# HSMC.net
KiCad netlist of a schematic drawn in Altium Designer
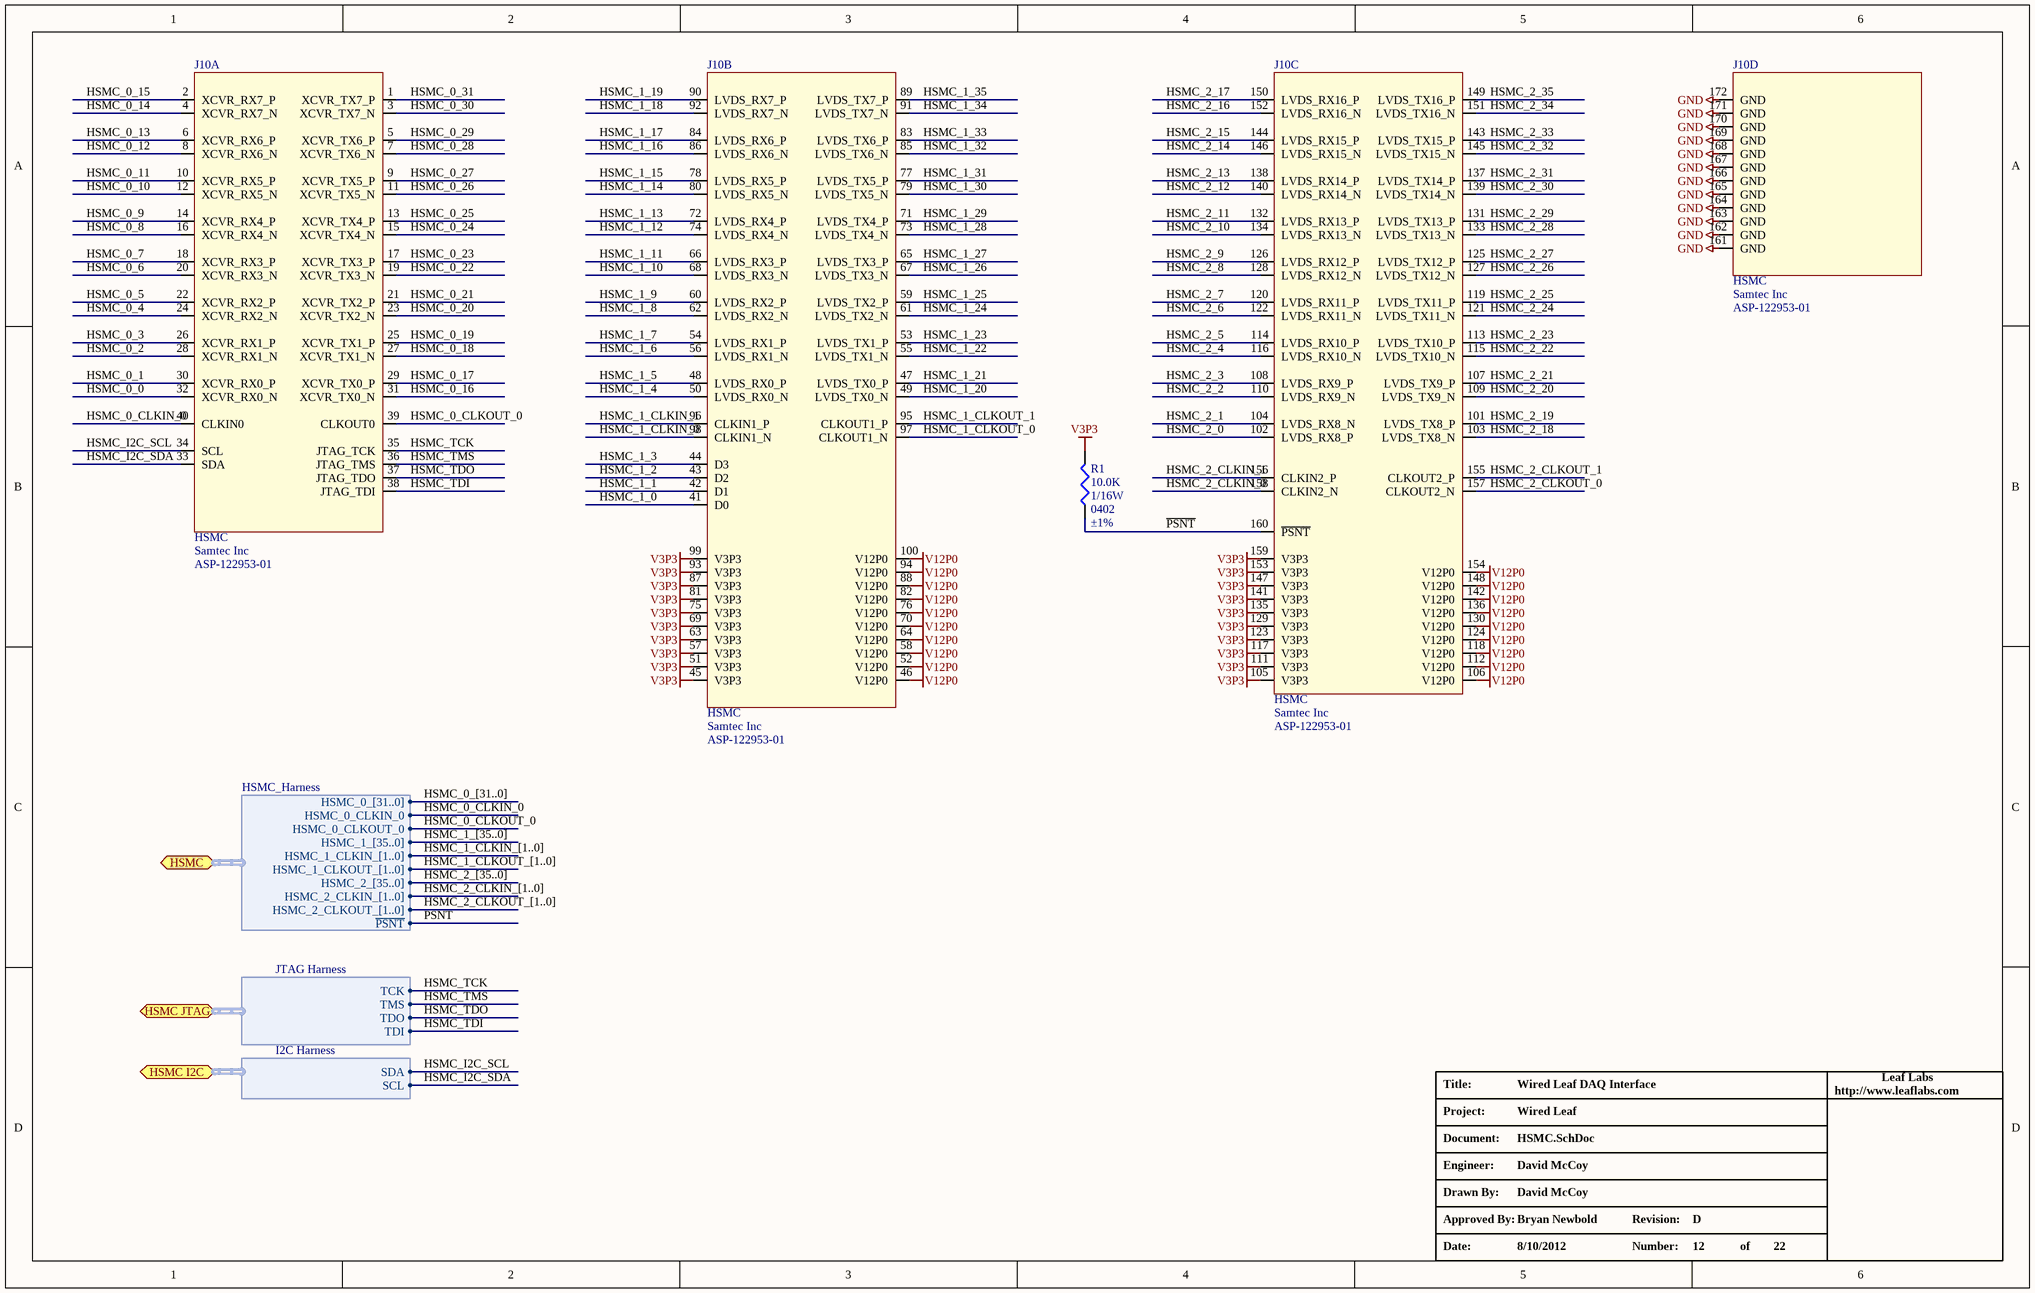
[diagram p0: HSMC.SchDoc]

(export (version "E")
  (design (tool "Eeschema 10.0.6"))
  (components
    (comp (ref "J10")
      (value "HSMC")
      (footprint "ASP-122953-01-ND")
      (description "CONN RECPT 60POS .020\" SMT GOLD")
      (fields
        (field (name "MANUFACTURER") "Samtec Inc")
        (field (name "MANUFACTURER PART NUMBER") "ASP-122953-01")
      )
      (libsource (lib "Main LibraryX") (part "J_HSMC"))
    )
    (comp (ref "R1")
      (value "R_0402_10.0K")
      (footprint "ERA-0402")
      (description "RES 10.0K OHM 1/16W 1% 0402 SMD")
      (fields
        (field (name "MANUFACTURER") "Vishay/Dale")
        (field (name "MANUFACTURER PART NUMBER") "CRCW040210K0FKED")
        (field (name "RESISTANCE IN OHMS") "10.0K")
        (field (name "POWER (WATTS)") "1/16W")
        (field (name "CASE") "0402")
        (field (name "TOLERANCE") "±1%")
      )
      (libsource (lib "Main Library") (part "R_0402_10.0K"))
    )
  )
  (nets
    (net (code "5") (name "/HSMC_0_0") (class "Default")
      (node (ref "J10") (pin "32") (pinfunction "XCVR_RX0_N_32") (pintype "passive"))
    )
    (net (code "6") (name "/HSMC_0_1") (class "Default")
      (node (ref "J10") (pin "30") (pinfunction "XCVR_RX0_P_30") (pintype "passive"))
    )
    (net (code "7") (name "/HSMC_0_2") (class "Default")
      (node (ref "J10") (pin "28") (pinfunction "XCVR_RX1_N_28") (pintype "passive"))
    )
    (net (code "8") (name "/HSMC_0_3") (class "Default")
      (node (ref "J10") (pin "26") (pinfunction "XCVR_RX1_P_26") (pintype "passive"))
    )
    (net (code "9") (name "/HSMC_0_4") (class "Default")
      (node (ref "J10") (pin "24") (pinfunction "XCVR_RX2_N_24") (pintype "passive"))
    )
    (net (code "10") (name "/HSMC_0_5") (class "Default")
      (node (ref "J10") (pin "22") (pinfunction "XCVR_RX2_P_22") (pintype "passive"))
    )
    (net (code "11") (name "/HSMC_0_6") (class "Default")
      (node (ref "J10") (pin "20") (pinfunction "XCVR_RX3_N_20") (pintype "passive"))
    )
    (net (code "12") (name "/HSMC_0_7") (class "Default")
      (node (ref "J10") (pin "18") (pinfunction "XCVR_RX3_P_18") (pintype "passive"))
    )
    (net (code "13") (name "/HSMC_0_8") (class "Default")
      (node (ref "J10") (pin "16") (pinfunction "XCVR_RX4_N_16") (pintype "passive"))
    )
    (net (code "14") (name "/HSMC_0_9") (class "Default")
      (node (ref "J10") (pin "14") (pinfunction "XCVR_RX4_P_14") (pintype "passive"))
    )
    (net (code "15") (name "/HSMC_0_10") (class "Default")
      (node (ref "J10") (pin "12") (pinfunction "XCVR_RX5_N_12") (pintype "passive"))
    )
    (net (code "16") (name "/HSMC_0_11") (class "Default")
      (node (ref "J10") (pin "10") (pinfunction "XCVR_RX5_P_10") (pintype "passive"))
    )
    (net (code "17") (name "/HSMC_0_12") (class "Default")
      (node (ref "J10") (pin "8") (pinfunction "XCVR_RX6_N_8") (pintype "passive"))
    )
    (net (code "18") (name "/HSMC_0_13") (class "Default")
      (node (ref "J10") (pin "6") (pinfunction "XCVR_RX6_P_6") (pintype "passive"))
    )
    (net (code "19") (name "/HSMC_0_14") (class "Default")
      (node (ref "J10") (pin "4") (pinfunction "XCVR_RX7_N_4") (pintype "passive"))
    )
    (net (code "20") (name "/HSMC_0_15") (class "Default")
      (node (ref "J10") (pin "2") (pinfunction "XCVR_RX7_P_2") (pintype "passive"))
    )
    (net (code "21") (name "/HSMC_0_16") (class "Default")
      (node (ref "J10") (pin "31") (pinfunction "XCVR_TX0_N_31") (pintype "passive"))
    )
    (net (code "22") (name "/HSMC_0_17") (class "Default")
      (node (ref "J10") (pin "29") (pinfunction "XCVR_TX0_P_29") (pintype "passive"))
    )
    (net (code "23") (name "/HSMC_0_18") (class "Default")
      (node (ref "J10") (pin "27") (pinfunction "XCVR_TX1_N_27") (pintype "passive"))
    )
    (net (code "24") (name "/HSMC_0_19") (class "Default")
      (node (ref "J10") (pin "25") (pinfunction "XCVR_TX1_P_25") (pintype "passive"))
    )
    (net (code "25") (name "/HSMC_0_20") (class "Default")
      (node (ref "J10") (pin "23") (pinfunction "XCVR_TX2_N_23") (pintype "passive"))
    )
    (net (code "26") (name "/HSMC_0_21") (class "Default")
      (node (ref "J10") (pin "21") (pinfunction "XCVR_TX2_P_21") (pintype "passive"))
    )
    (net (code "27") (name "/HSMC_0_22") (class "Default")
      (node (ref "J10") (pin "19") (pinfunction "XCVR_TX3_N_19") (pintype "passive"))
    )
    (net (code "28") (name "/HSMC_0_23") (class "Default")
      (node (ref "J10") (pin "17") (pinfunction "XCVR_TX3_P_17") (pintype "passive"))
    )
    (net (code "29") (name "/HSMC_0_24") (class "Default")
      (node (ref "J10") (pin "15") (pinfunction "XCVR_TX4_N_15") (pintype "passive"))
    )
    (net (code "30") (name "/HSMC_0_25") (class "Default")
      (node (ref "J10") (pin "13") (pinfunction "XCVR_TX4_P_13") (pintype "passive"))
    )
    (net (code "31") (name "/HSMC_0_26") (class "Default")
      (node (ref "J10") (pin "11") (pinfunction "XCVR_TX5_N_11") (pintype "passive"))
    )
    (net (code "32") (name "/HSMC_0_27") (class "Default")
      (node (ref "J10") (pin "9") (pinfunction "XCVR_TX5_P_9") (pintype "passive"))
    )
    (net (code "33") (name "/HSMC_0_28") (class "Default")
      (node (ref "J10") (pin "7") (pinfunction "XCVR_TX6_N_7") (pintype "passive"))
    )
    (net (code "34") (name "/HSMC_0_29") (class "Default")
      (node (ref "J10") (pin "5") (pinfunction "XCVR_TX6_P_5") (pintype "passive"))
    )
    (net (code "35") (name "/HSMC_0_30") (class "Default")
      (node (ref "J10") (pin "3") (pinfunction "XCVR_TX7_N_3") (pintype "passive"))
    )
    (net (code "36") (name "/HSMC_0_31") (class "Default")
      (node (ref "J10") (pin "1") (pinfunction "XCVR_TX7_P_1") (pintype "passive"))
    )
    (net (code "37") (name "/HSMC_0_CLKIN_0") (class "Default")
      (node (ref "J10") (pin "40") (pinfunction "CLKIN0_40") (pintype "passive"))
    )
    (net (code "38") (name "/HSMC_0_CLKOUT_0") (class "Default")
      (node (ref "J10") (pin "39") (pinfunction "CLKOUT0_39") (pintype "passive"))
    )
    (net (code "40") (name "/HSMC_1_0") (class "Default")
      (node (ref "J10") (pin "41") (pinfunction "D0_41") (pintype "passive"))
    )
    (net (code "41") (name "/HSMC_1_1") (class "Default")
      (node (ref "J10") (pin "42") (pinfunction "D1_42") (pintype "passive"))
    )
    (net (code "42") (name "/HSMC_1_2") (class "Default")
      (node (ref "J10") (pin "43") (pinfunction "D2_43") (pintype "passive"))
    )
    (net (code "43") (name "/HSMC_1_3") (class "Default")
      (node (ref "J10") (pin "44") (pinfunction "D3_44") (pintype "passive"))
    )
    (net (code "44") (name "/HSMC_1_4") (class "Default")
      (node (ref "J10") (pin "50") (pinfunction "LVDS_RX0_N_50") (pintype "passive"))
    )
    (net (code "45") (name "/HSMC_1_5") (class "Default")
      (node (ref "J10") (pin "48") (pinfunction "LVDS_RX0_P_48") (pintype "passive"))
    )
    (net (code "46") (name "/HSMC_1_6") (class "Default")
      (node (ref "J10") (pin "56") (pinfunction "LVDS_RX1_N_56") (pintype "passive"))
    )
    (net (code "47") (name "/HSMC_1_7") (class "Default")
      (node (ref "J10") (pin "54") (pinfunction "LVDS_RX1_P_54") (pintype "passive"))
    )
    (net (code "48") (name "/HSMC_1_8") (class "Default")
      (node (ref "J10") (pin "62") (pinfunction "LVDS_RX2_N_62") (pintype "passive"))
    )
    (net (code "49") (name "/HSMC_1_9") (class "Default")
      (node (ref "J10") (pin "60") (pinfunction "LVDS_RX2_P_60") (pintype "passive"))
    )
    (net (code "50") (name "/HSMC_1_10") (class "Default")
      (node (ref "J10") (pin "68") (pinfunction "LVDS_RX3_N_68") (pintype "passive"))
    )
    (net (code "51") (name "/HSMC_1_11") (class "Default")
      (node (ref "J10") (pin "66") (pinfunction "LVDS_RX3_P_66") (pintype "passive"))
    )
    (net (code "52") (name "/HSMC_1_12") (class "Default")
      (node (ref "J10") (pin "74") (pinfunction "LVDS_RX4_N_74") (pintype "passive"))
    )
    (net (code "53") (name "/HSMC_1_13") (class "Default")
      (node (ref "J10") (pin "72") (pinfunction "LVDS_RX4_P_72") (pintype "passive"))
    )
    (net (code "54") (name "/HSMC_1_14") (class "Default")
      (node (ref "J10") (pin "80") (pinfunction "LVDS_RX5_N_80") (pintype "passive"))
    )
    (net (code "55") (name "/HSMC_1_15") (class "Default")
      (node (ref "J10") (pin "78") (pinfunction "LVDS_RX5_P_78") (pintype "passive"))
    )
    (net (code "56") (name "/HSMC_1_16") (class "Default")
      (node (ref "J10") (pin "86") (pinfunction "LVDS_RX6_N_86") (pintype "passive"))
    )
    (net (code "57") (name "/HSMC_1_17") (class "Default")
      (node (ref "J10") (pin "84") (pinfunction "LVDS_RX6_P_84") (pintype "passive"))
    )
    (net (code "58") (name "/HSMC_1_18") (class "Default")
      (node (ref "J10") (pin "92") (pinfunction "LVDS_RX7_N_92") (pintype "passive"))
    )
    (net (code "59") (name "/HSMC_1_19") (class "Default")
      (node (ref "J10") (pin "90") (pinfunction "LVDS_RX7_P_90") (pintype "passive"))
    )
    (net (code "60") (name "/HSMC_1_20") (class "Default")
      (node (ref "J10") (pin "49") (pinfunction "LVDS_TX0_N_49") (pintype "passive"))
    )
    (net (code "61") (name "/HSMC_1_21") (class "Default")
      (node (ref "J10") (pin "47") (pinfunction "LVDS_TX0_P_47") (pintype "passive"))
    )
    (net (code "62") (name "/HSMC_1_22") (class "Default")
      (node (ref "J10") (pin "55") (pinfunction "LVDS_TX1_N_55") (pintype "passive"))
    )
    (net (code "63") (name "/HSMC_1_23") (class "Default")
      (node (ref "J10") (pin "53") (pinfunction "LVDS_TX1_P_53") (pintype "passive"))
    )
    (net (code "64") (name "/HSMC_1_24") (class "Default")
      (node (ref "J10") (pin "61") (pinfunction "LVDS_TX2_N_61") (pintype "passive"))
    )
    (net (code "65") (name "/HSMC_1_25") (class "Default")
      (node (ref "J10") (pin "59") (pinfunction "LVDS_TX2_P_59") (pintype "passive"))
    )
    (net (code "66") (name "/HSMC_1_26") (class "Default")
      (node (ref "J10") (pin "67") (pinfunction "LVDS_TX3_N_67") (pintype "passive"))
    )
    (net (code "67") (name "/HSMC_1_27") (class "Default")
      (node (ref "J10") (pin "65") (pinfunction "LVDS_TX3_P_65") (pintype "passive"))
    )
    (net (code "68") (name "/HSMC_1_28") (class "Default")
      (node (ref "J10") (pin "73") (pinfunction "LVDS_TX4_N_73") (pintype "passive"))
    )
    (net (code "69") (name "/HSMC_1_29") (class "Default")
      (node (ref "J10") (pin "71") (pinfunction "LVDS_TX4_P_71") (pintype "passive"))
    )
    (net (code "70") (name "/HSMC_1_30") (class "Default")
      (node (ref "J10") (pin "79") (pinfunction "LVDS_TX5_N_79") (pintype "passive"))
    )
    (net (code "71") (name "/HSMC_1_31") (class "Default")
      (node (ref "J10") (pin "77") (pinfunction "LVDS_TX5_P_77") (pintype "passive"))
    )
    (net (code "72") (name "/HSMC_1_32") (class "Default")
      (node (ref "J10") (pin "85") (pinfunction "LVDS_TX6_N_85") (pintype "passive"))
    )
    (net (code "73") (name "/HSMC_1_33") (class "Default")
      (node (ref "J10") (pin "83") (pinfunction "LVDS_TX6_P_83") (pintype "passive"))
    )
    (net (code "74") (name "/HSMC_1_34") (class "Default")
      (node (ref "J10") (pin "91") (pinfunction "LVDS_TX7_N_91") (pintype "passive"))
    )
    (net (code "75") (name "/HSMC_1_35") (class "Default")
      (node (ref "J10") (pin "89") (pinfunction "LVDS_TX7_P_89") (pintype "passive"))
    )
    (net (code "76") (name "/HSMC_1_CLKIN_0") (class "Default")
      (node (ref "J10") (pin "98") (pinfunction "CLKIN1_N_98") (pintype "passive"))
    )
    (net (code "77") (name "/HSMC_1_CLKIN_1") (class "Default")
      (node (ref "J10") (pin "96") (pinfunction "CLKIN1_P_96") (pintype "passive"))
    )
    (net (code "79") (name "/HSMC_1_CLKOUT_0") (class "Default")
      (node (ref "J10") (pin "97") (pinfunction "CLKOUT1_N_97") (pintype "passive"))
    )
    (net (code "80") (name "/HSMC_1_CLKOUT_1") (class "Default")
      (node (ref "J10") (pin "95") (pinfunction "CLKOUT1_P_95") (pintype "passive"))
    )
    (net (code "83") (name "/HSMC_2_0") (class "Default")
      (node (ref "J10") (pin "102") (pinfunction "LVDS_RX8_P_102") (pintype "passive"))
    )
    (net (code "84") (name "/HSMC_2_1") (class "Default")
      (node (ref "J10") (pin "104") (pinfunction "LVDS_RX8_N_104") (pintype "passive"))
    )
    (net (code "85") (name "/HSMC_2_2") (class "Default")
      (node (ref "J10") (pin "110") (pinfunction "LVDS_RX9_N_110") (pintype "passive"))
    )
    (net (code "86") (name "/HSMC_2_3") (class "Default")
      (node (ref "J10") (pin "108") (pinfunction "LVDS_RX9_P_108") (pintype "passive"))
    )
    (net (code "87") (name "/HSMC_2_4") (class "Default")
      (node (ref "J10") (pin "116") (pinfunction "LVDS_RX10_N_116") (pintype "passive"))
    )
    (net (code "88") (name "/HSMC_2_5") (class "Default")
      (node (ref "J10") (pin "114") (pinfunction "LVDS_RX10_P_114") (pintype "passive"))
    )
    (net (code "89") (name "/HSMC_2_6") (class "Default")
      (node (ref "J10") (pin "122") (pinfunction "LVDS_RX11_N_122") (pintype "passive"))
    )
    (net (code "90") (name "/HSMC_2_7") (class "Default")
      (node (ref "J10") (pin "120") (pinfunction "LVDS_RX11_P_120") (pintype "passive"))
    )
    (net (code "91") (name "/HSMC_2_8") (class "Default")
      (node (ref "J10") (pin "128") (pinfunction "LVDS_RX12_N_128") (pintype "passive"))
    )
    (net (code "92") (name "/HSMC_2_9") (class "Default")
      (node (ref "J10") (pin "126") (pinfunction "LVDS_RX12_P_126") (pintype "passive"))
    )
    (net (code "93") (name "/HSMC_2_10") (class "Default")
      (node (ref "J10") (pin "134") (pinfunction "LVDS_RX13_N_134") (pintype "passive"))
    )
    (net (code "94") (name "/HSMC_2_11") (class "Default")
      (node (ref "J10") (pin "132") (pinfunction "LVDS_RX13_P_132") (pintype "passive"))
    )
    (net (code "95") (name "/HSMC_2_12") (class "Default")
      (node (ref "J10") (pin "140") (pinfunction "LVDS_RX14_N_140") (pintype "passive"))
    )
    (net (code "96") (name "/HSMC_2_13") (class "Default")
      (node (ref "J10") (pin "138") (pinfunction "LVDS_RX14_P_138") (pintype "passive"))
    )
    (net (code "97") (name "/HSMC_2_14") (class "Default")
      (node (ref "J10") (pin "146") (pinfunction "LVDS_RX15_N_146") (pintype "passive"))
    )
    (net (code "98") (name "/HSMC_2_15") (class "Default")
      (node (ref "J10") (pin "144") (pinfunction "LVDS_RX15_P_144") (pintype "passive"))
    )
    (net (code "99") (name "/HSMC_2_16") (class "Default")
      (node (ref "J10") (pin "152") (pinfunction "LVDS_RX16_N_152") (pintype "passive"))
    )
    (net (code "100") (name "/HSMC_2_17") (class "Default")
      (node (ref "J10") (pin "150") (pinfunction "LVDS_RX16_P_150") (pintype "passive"))
    )
    (net (code "101") (name "/HSMC_2_18") (class "Default")
      (node (ref "J10") (pin "103") (pinfunction "LVDS_TX8_N_103") (pintype "passive"))
    )
    (net (code "102") (name "/HSMC_2_19") (class "Default")
      (node (ref "J10") (pin "101") (pinfunction "LVDS_TX8_P_101") (pintype "passive"))
    )
    (net (code "103") (name "/HSMC_2_20") (class "Default")
      (node (ref "J10") (pin "109") (pinfunction "LVDS_TX9_N_109") (pintype "passive"))
    )
    (net (code "104") (name "/HSMC_2_21") (class "Default")
      (node (ref "J10") (pin "107") (pinfunction "LVDS_TX9_P_107") (pintype "passive"))
    )
    (net (code "105") (name "/HSMC_2_22") (class "Default")
      (node (ref "J10") (pin "115") (pinfunction "LVDS_TX10_N_115") (pintype "passive"))
    )
    (net (code "106") (name "/HSMC_2_23") (class "Default")
      (node (ref "J10") (pin "113") (pinfunction "LVDS_TX10_P_113") (pintype "passive"))
    )
    (net (code "107") (name "/HSMC_2_24") (class "Default")
      (node (ref "J10") (pin "121") (pinfunction "LVDS_TX11_N_121") (pintype "passive"))
    )
    (net (code "108") (name "/HSMC_2_25") (class "Default")
      (node (ref "J10") (pin "119") (pinfunction "LVDS_TX11_P_119") (pintype "passive"))
    )
    (net (code "109") (name "/HSMC_2_26") (class "Default")
      (node (ref "J10") (pin "127") (pinfunction "LVDS_TX12_N_127") (pintype "passive"))
    )
    (net (code "110") (name "/HSMC_2_27") (class "Default")
      (node (ref "J10") (pin "125") (pinfunction "LVDS_TX12_P_125") (pintype "passive"))
    )
    (net (code "111") (name "/HSMC_2_28") (class "Default")
      (node (ref "J10") (pin "133") (pinfunction "LVDS_TX13_N_133") (pintype "passive"))
    )
    (net (code "112") (name "/HSMC_2_29") (class "Default")
      (node (ref "J10") (pin "131") (pinfunction "LVDS_TX13_P_131") (pintype "passive"))
    )
    (net (code "113") (name "/HSMC_2_30") (class "Default")
      (node (ref "J10") (pin "139") (pinfunction "LVDS_TX14_N_139") (pintype "passive"))
    )
    (net (code "114") (name "/HSMC_2_31") (class "Default")
      (node (ref "J10") (pin "137") (pinfunction "LVDS_TX14_P_137") (pintype "passive"))
    )
    (net (code "115") (name "/HSMC_2_32") (class "Default")
      (node (ref "J10") (pin "145") (pinfunction "LVDS_TX15_N_145") (pintype "passive"))
    )
    (net (code "116") (name "/HSMC_2_33") (class "Default")
      (node (ref "J10") (pin "143") (pinfunction "LVDS_TX15_P_143") (pintype "passive"))
    )
    (net (code "117") (name "/HSMC_2_34") (class "Default")
      (node (ref "J10") (pin "151") (pinfunction "LVDS_TX16_N_151") (pintype "passive"))
    )
    (net (code "118") (name "/HSMC_2_35") (class "Default")
      (node (ref "J10") (pin "149") (pinfunction "LVDS_TX16_P_149") (pintype "passive"))
    )
    (net (code "119") (name "/HSMC_2_CLKIN_0") (class "Default")
      (node (ref "J10") (pin "158") (pinfunction "CLKIN2_N_158") (pintype "passive"))
    )
    (net (code "120") (name "/HSMC_2_CLKIN_1") (class "Default")
      (node (ref "J10") (pin "156") (pinfunction "CLKIN2_P_156") (pintype "passive"))
    )
    (net (code "122") (name "/HSMC_2_CLKOUT_0") (class "Default")
      (node (ref "J10") (pin "157") (pinfunction "CLKOUT2_N_157") (pintype "passive"))
    )
    (net (code "123") (name "/HSMC_2_CLKOUT_1") (class "Default")
      (node (ref "J10") (pin "155") (pinfunction "CLKOUT2_P_155") (pintype "passive"))
    )
    (net (code "125") (name "/HSMC_I2C_SCL") (class "Default")
      (node (ref "J10") (pin "34") (pinfunction "SCL_34") (pintype "passive"))
    )
    (net (code "126") (name "/HSMC_I2C_SDA") (class "Default")
      (node (ref "J10") (pin "33") (pinfunction "SDA_33") (pintype "passive"))
    )
    (net (code "127") (name "/HSMC_TCK") (class "Default")
      (node (ref "J10") (pin "35") (pinfunction "JTAG_TCK_35") (pintype "passive"))
    )
    (net (code "128") (name "/HSMC_TDI") (class "Default")
      (node (ref "J10") (pin "38") (pinfunction "JTAG_TDI_38") (pintype "passive"))
    )
    (net (code "129") (name "/HSMC_TDO") (class "Default")
      (node (ref "J10") (pin "37") (pinfunction "JTAG_TDO_37") (pintype "passive"))
    )
    (net (code "130") (name "/HSMC_TMS") (class "Default")
      (node (ref "J10") (pin "36") (pinfunction "JTAG_TMS_36") (pintype "passive"))
    )
    (net (code "135") (name "/~{PSNT}") (class "Default")
      (node (ref "J10") (pin "160") (pinfunction "~{PSNT}_160") (pintype "passive"))
      (node (ref "R1") (pin "2") (pinfunction "2_2") (pintype "passive"))
    )
    (net (code "136") (name "GND") (class "Default")
      (node (ref "J10") (pin "161") (pinfunction "GND_161") (pintype "passive"))
      (node (ref "J10") (pin "162") (pinfunction "GND_162") (pintype "passive"))
      (node (ref "J10") (pin "163") (pinfunction "GND_163") (pintype "passive"))
      (node (ref "J10") (pin "164") (pinfunction "GND_164") (pintype "passive"))
      (node (ref "J10") (pin "165") (pinfunction "GND_165") (pintype "passive"))
      (node (ref "J10") (pin "166") (pinfunction "GND_166") (pintype "passive"))
      (node (ref "J10") (pin "167") (pinfunction "GND_167") (pintype "passive"))
      (node (ref "J10") (pin "168") (pinfunction "GND_168") (pintype "passive"))
      (node (ref "J10") (pin "169") (pinfunction "GND_169") (pintype "passive"))
      (node (ref "J10") (pin "170") (pinfunction "GND_170") (pintype "passive"))
      (node (ref "J10") (pin "171") (pinfunction "GND_171") (pintype "passive"))
      (node (ref "J10") (pin "172") (pinfunction "GND_172") (pintype "passive"))
    )
    (net (code "137") (name "V3P3") (class "Default")
      (node (ref "J10") (pin "105") (pinfunction "V3P3_105") (pintype "passive"))
      (node (ref "J10") (pin "111") (pinfunction "V3P3_111") (pintype "passive"))
      (node (ref "J10") (pin "117") (pinfunction "V3P3_117") (pintype "passive"))
      (node (ref "J10") (pin "123") (pinfunction "V3P3_123") (pintype "passive"))
      (node (ref "J10") (pin "129") (pinfunction "V3P3_129") (pintype "passive"))
      (node (ref "J10") (pin "135") (pinfunction "V3P3_135") (pintype "passive"))
      (node (ref "J10") (pin "141") (pinfunction "V3P3_141") (pintype "passive"))
      (node (ref "J10") (pin "147") (pinfunction "V3P3_147") (pintype "passive"))
      (node (ref "J10") (pin "153") (pinfunction "V3P3_153") (pintype "passive"))
      (node (ref "J10") (pin "159") (pinfunction "V3P3_159") (pintype "passive"))
      (node (ref "J10") (pin "45") (pinfunction "V3P3_45") (pintype "passive"))
      (node (ref "J10") (pin "51") (pinfunction "V3P3_51") (pintype "passive"))
      (node (ref "J10") (pin "57") (pinfunction "V3P3_57") (pintype "passive"))
      (node (ref "J10") (pin "63") (pinfunction "V3P3_63") (pintype "passive"))
      (node (ref "J10") (pin "69") (pinfunction "V3P3_69") (pintype "passive"))
      (node (ref "J10") (pin "75") (pinfunction "V3P3_75") (pintype "passive"))
      (node (ref "J10") (pin "81") (pinfunction "V3P3_81") (pintype "passive"))
      (node (ref "J10") (pin "87") (pinfunction "V3P3_87") (pintype "passive"))
      (node (ref "J10") (pin "93") (pinfunction "V3P3_93") (pintype "passive"))
      (node (ref "J10") (pin "99") (pinfunction "V3P3_99") (pintype "passive"))
      (node (ref "R1") (pin "1") (pinfunction "1_1") (pintype "passive"))
    )
    (net (code "138") (name "V12P0") (class "Default")
      (node (ref "J10") (pin "100") (pinfunction "V12P0_100") (pintype "passive"))
      (node (ref "J10") (pin "106") (pinfunction "V12P0_106") (pintype "passive"))
      (node (ref "J10") (pin "112") (pinfunction "V12P0_112") (pintype "passive"))
      (node (ref "J10") (pin "118") (pinfunction "V12P0_118") (pintype "passive"))
      (node (ref "J10") (pin "124") (pinfunction "V12P0_124") (pintype "passive"))
      (node (ref "J10") (pin "130") (pinfunction "V12P0_130") (pintype "passive"))
      (node (ref "J10") (pin "136") (pinfunction "V12P0_136") (pintype "passive"))
      (node (ref "J10") (pin "142") (pinfunction "V12P0_142") (pintype "passive"))
      (node (ref "J10") (pin "148") (pinfunction "V12P0_148") (pintype "passive"))
      (node (ref "J10") (pin "154") (pinfunction "V12P0_154") (pintype "passive"))
      (node (ref "J10") (pin "46") (pinfunction "V12P0_46") (pintype "passive"))
      (node (ref "J10") (pin "52") (pinfunction "V12P0_52") (pintype "passive"))
      (node (ref "J10") (pin "58") (pinfunction "V12P0_58") (pintype "passive"))
      (node (ref "J10") (pin "64") (pinfunction "V12P0_64") (pintype "passive"))
      (node (ref "J10") (pin "70") (pinfunction "V12P0_70") (pintype "passive"))
      (node (ref "J10") (pin "76") (pinfunction "V12P0_76") (pintype "passive"))
      (node (ref "J10") (pin "82") (pinfunction "V12P0_82") (pintype "passive"))
      (node (ref "J10") (pin "88") (pinfunction "V12P0_88") (pintype "passive"))
      (node (ref "J10") (pin "94") (pinfunction "V12P0_94") (pintype "passive"))
    )
  )
)
